# Root.net
KiCad netlist of a schematic drawn in Altium Designer
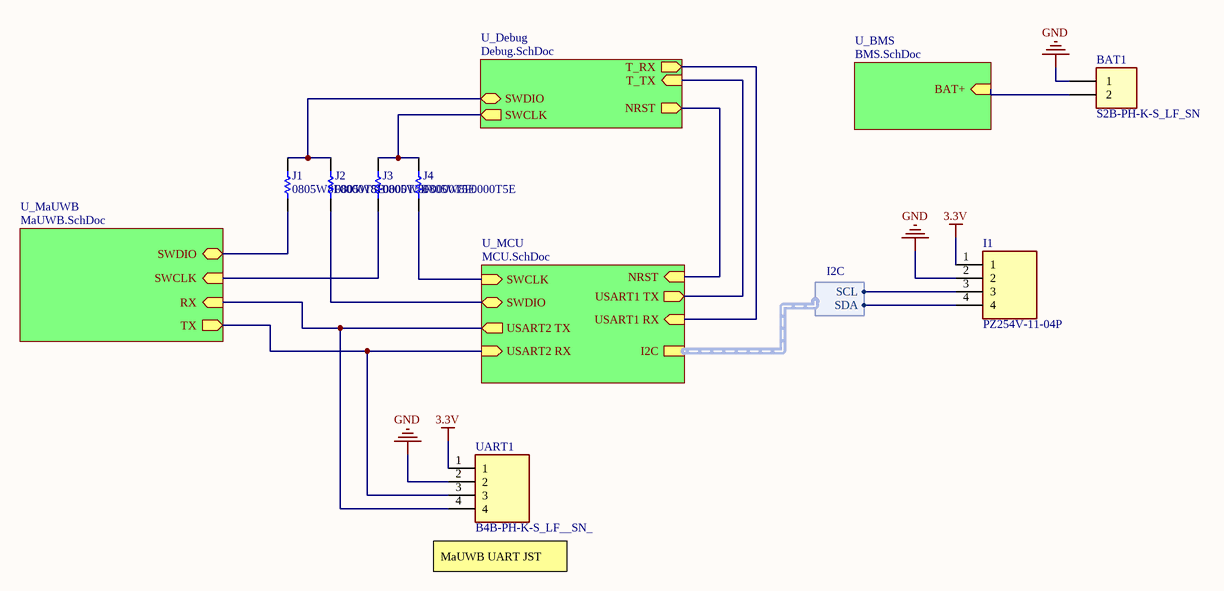
[diagram p0: Root.SchDoc]

(export (version "E")
  (design (tool "Eeschema 10.0.6"))
  (components
    (comp (ref "BAT1")
      (value "S2B-PH-K-S_LF_SN")
      (footprint "S2B-PH-K-S_LF_SN")
      (fields
        (field (name "LCSC PART #") "C173752")
        (field (name "MANUFACTURER") "JST")
        (field (name "MANU PART #") "S2B-PH-K-S(LF)(SN)")
      )
      (libsource (lib "MaUWB") (part "S2B-PH-K-S_LF_SN"))
    )
    (comp (ref "I1")
      (value "PZ254V-11-04P")
      (footprint "HDRV4W64P0X254_1X4_1016X250X890P")
      (description "4 pin 2.54mm Header")
      (fields (field (name "LCSC PART #") "C2691448"))
      (libsource (lib "MaUWB") (part "PZ254V-11-04P"))
    )
    (comp (ref "J1")
      (value "0805W8F0000T5E")
      (footprint "RESC2013X65N - Duplicate1")
      (description "0 Ohm, 0805, 1%")
      (fields (field (name "LCSC PART #") "C17477"))
      (libsource (lib "MaUWB") (part "0805W8F0000T5E"))
    )
    (comp (ref "J2")
      (value "0805W8F0000T5E")
      (footprint "RESC2013X65N - Duplicate1")
      (description "0 Ohm, 0805, 1%")
      (fields (field (name "LCSC PART #") "C17477"))
      (libsource (lib "MaUWB") (part "0805W8F0000T5E"))
    )
    (comp (ref "J3")
      (value "0805W8F0000T5E")
      (footprint "RESC2013X65N - Duplicate1")
      (description "0 Ohm, 0805, 1%")
      (fields (field (name "LCSC PART #") "C17477"))
      (libsource (lib "MaUWB") (part "0805W8F0000T5E"))
    )
    (comp (ref "J4")
      (value "0805W8F0000T5E")
      (footprint "RESC2013X65N - Duplicate1")
      (description "0 Ohm, 0805, 1%")
      (fields (field (name "LCSC PART #") "C17477"))
      (libsource (lib "MaUWB") (part "0805W8F0000T5E"))
    )
    (comp (ref "UART1")
      (value "B4B-PH-K-S_LF__SN_")
      (footprint "SHDR4W50P0X200_1X4_990X450X600P")
      (description "JST 4 pin")
      (fields (field (name "LCSC PART #") "C131334") (field (name "MANU PART #") "B4B-PH-K-S(LF)(SN)"))
      (libsource (lib "MaUWB") (part "B4B-PH-K-S_LF__SN_"))
    )
  )
  (nets
    (net (code "2") (name "/BAT+") (class "Default")
      (node (ref "BAT1") (pin "2") (pinfunction "2_2") (pintype "passive"))
    )
    (net (code "4") (name "/SWCLK") (class "Default")
      (node (ref "J3") (pin "2") (pinfunction "2_2") (pintype "passive"))
      (node (ref "J4") (pin "2") (pinfunction "2_2") (pintype "passive"))
    )
    (net (code "5") (name "/SWCLK_1") (class "Default")
      (node (ref "J3") (pin "1") (pinfunction "1_1") (pintype "passive"))
    )
    (net (code "6") (name "/SWCLK_2") (class "Default")
      (node (ref "J4") (pin "1") (pinfunction "1_1") (pintype "passive"))
    )
    (net (code "7") (name "/SWDIO") (class "Default")
      (node (ref "J1") (pin "2") (pinfunction "2_2") (pintype "passive"))
      (node (ref "J2") (pin "2") (pinfunction "2_2") (pintype "passive"))
    )
    (net (code "8") (name "/SWDIO_1") (class "Default")
      (node (ref "J2") (pin "1") (pinfunction "1_1") (pintype "passive"))
    )
    (net (code "9") (name "/SWDIO_2") (class "Default")
      (node (ref "J1") (pin "1") (pinfunction "1_1") (pintype "passive"))
    )
    (net (code "10") (name "/TX") (class "Default")
      (node (ref "UART1") (pin "3") (pinfunction "3_3") (pintype "passive"))
    )
    (net (code "13") (name "/USART2 TX") (class "Default")
      (node (ref "UART1") (pin "4") (pinfunction "4_4") (pintype "passive"))
    )
    (net (code "15") (name "3.3V") (class "Default")
      (node (ref "I1") (pin "1") (pinfunction "1_1") (pintype "passive"))
      (node (ref "UART1") (pin "1") (pinfunction "1_1") (pintype "passive"))
    )
    (net (code "16") (name "GND") (class "Default")
      (node (ref "BAT1") (pin "1") (pinfunction "1_1") (pintype "passive"))
      (node (ref "I1") (pin "2") (pinfunction "2_2") (pintype "passive"))
      (node (ref "UART1") (pin "2") (pinfunction "2_2") (pintype "passive"))
    )
    (net (code "17") (name "unconnected-(I1-Pad3)") (class "Default")
      (node (ref "I1") (pin "3") (pinfunction "3_3") (pintype "passive"))
    )
    (net (code "18") (name "unconnected-(I1-Pad4)") (class "Default")
      (node (ref "I1") (pin "4") (pinfunction "4_4") (pintype "passive"))
    )
  )
)
